# rgbMatrix.net
KiCad netlist of a schematic drawn in EAGLE
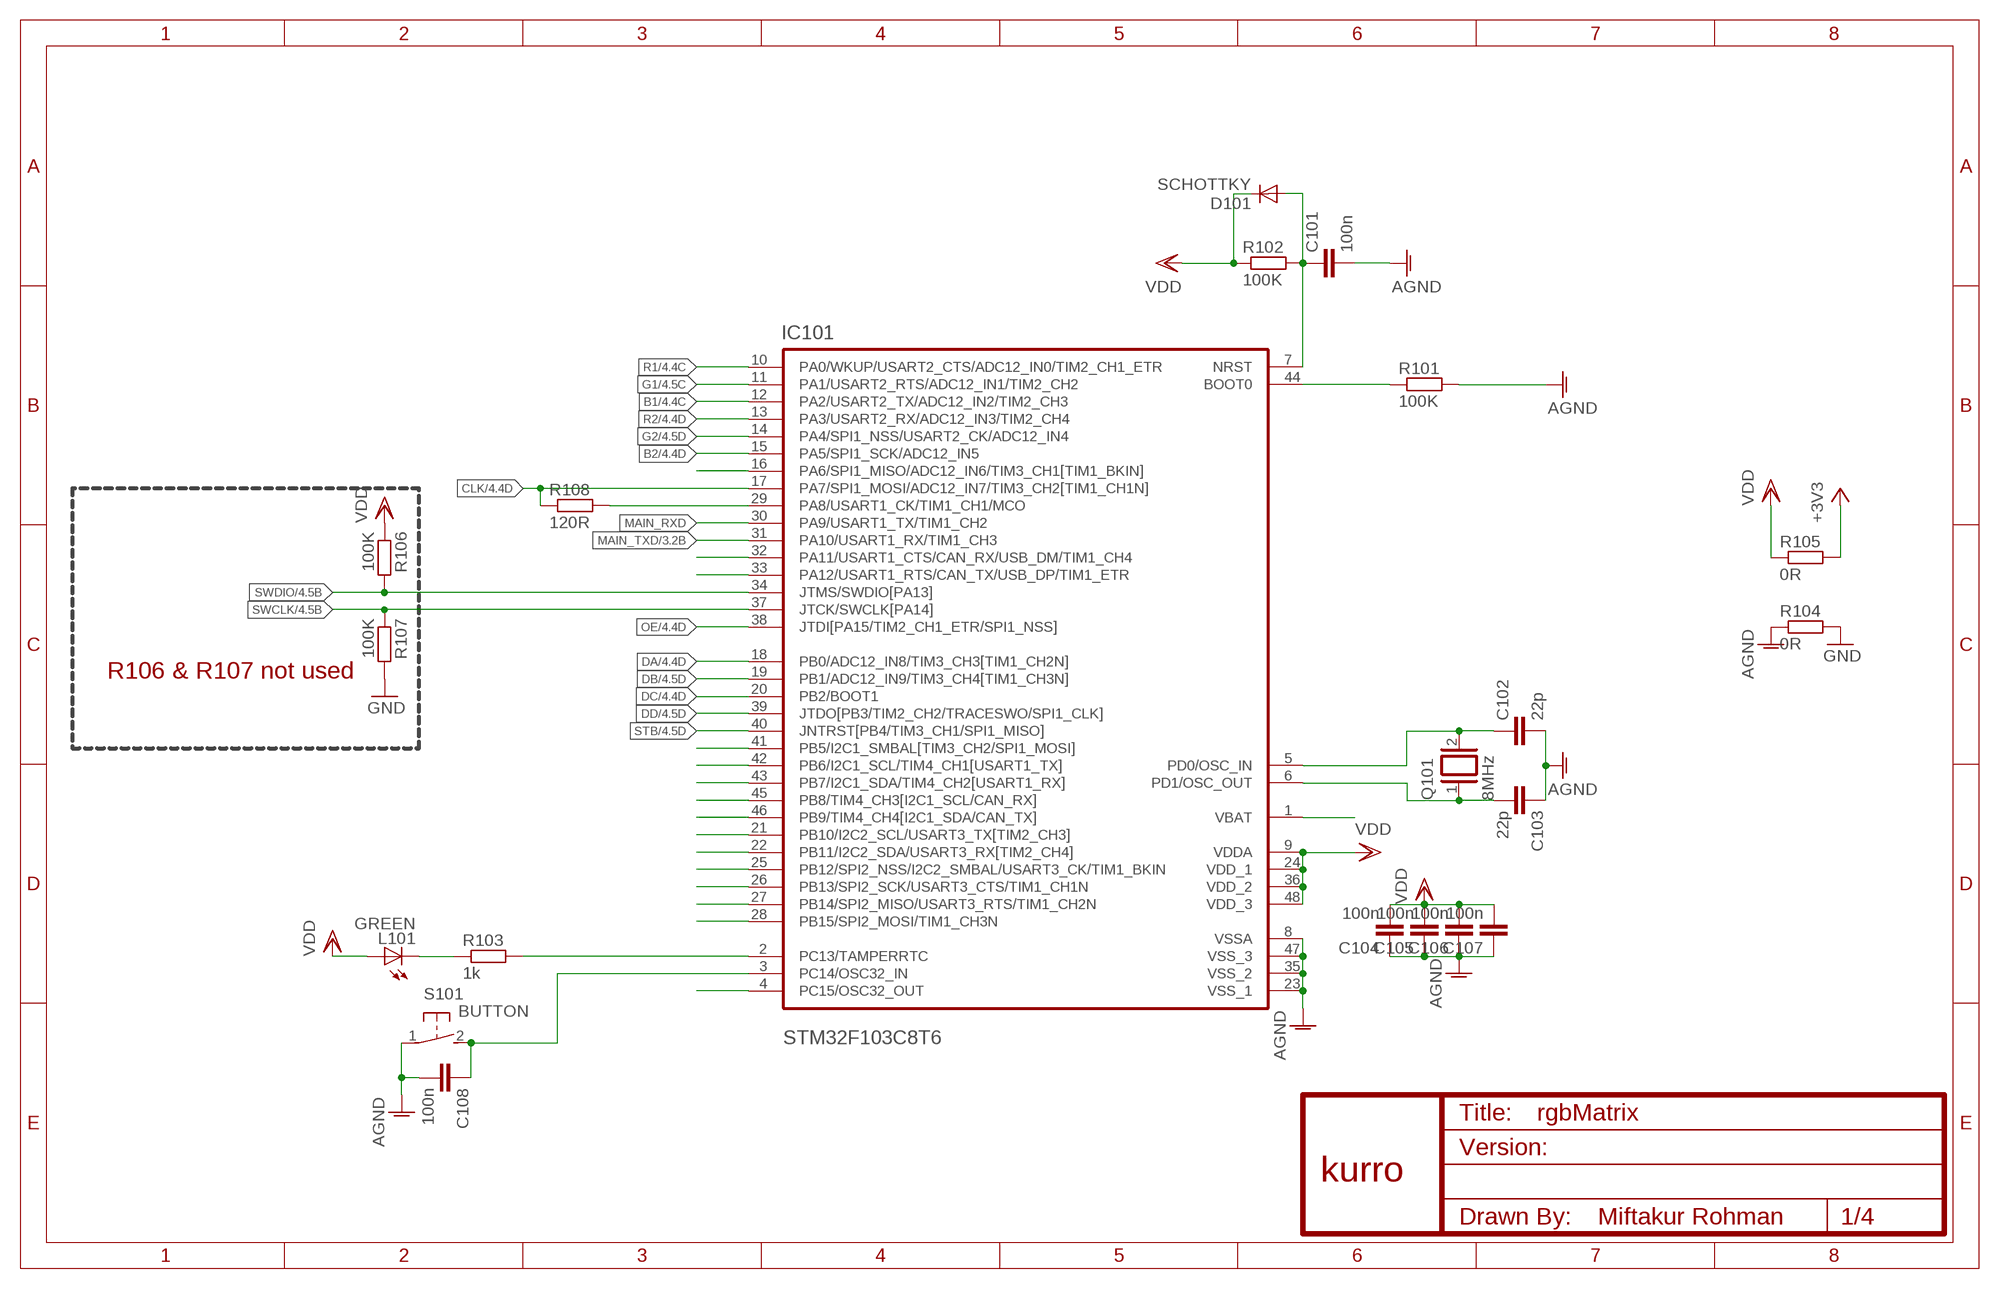
[diagram p0: schematic, sheet 1]
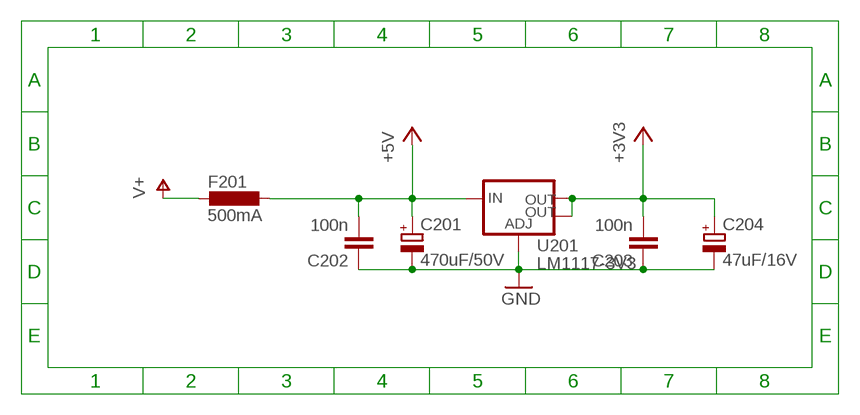
[diagram p1: schematic, sheet 2]
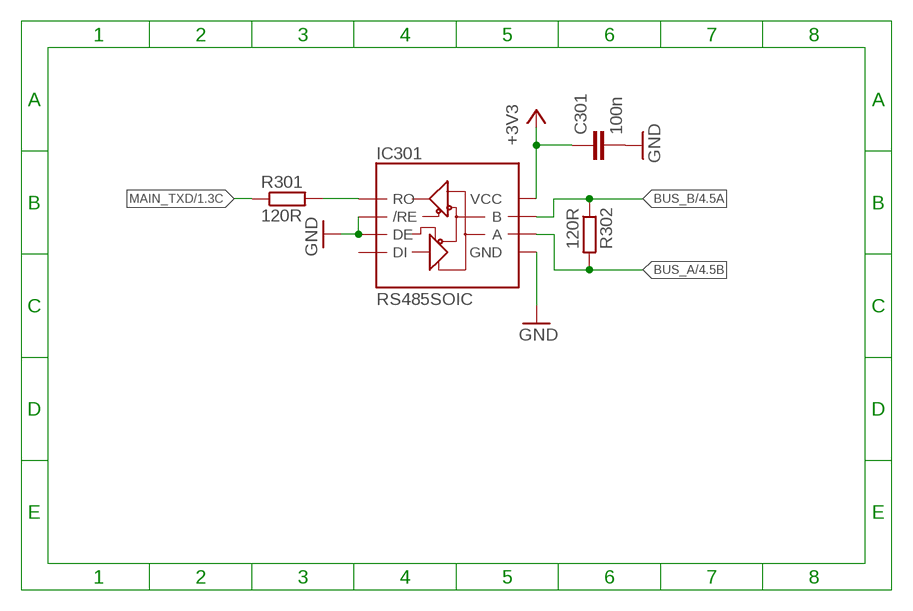
[diagram p2: schematic, sheet 3]
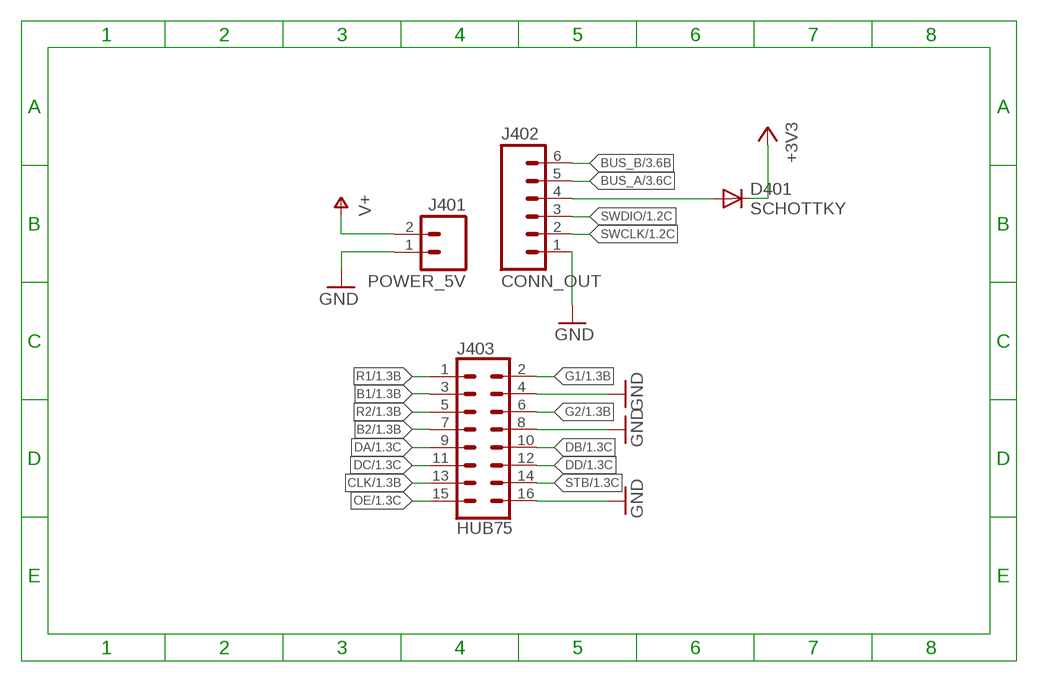
[diagram p3: schematic, sheet 4]

(export (version "E")
  (design (tool "Eeschema 10.0.6"))
  (components
    (comp (ref "C101")
      (value "100n")
      (footprint "eagle-import:C0603")
      (libsource (lib "eagle-import") (part "C-EUC0603"))
    )
    (comp (ref "C102")
      (value "22p")
      (footprint "eagle-import:C0603")
      (libsource (lib "eagle-import") (part "C-EUC0603"))
    )
    (comp (ref "C103")
      (value "22p")
      (footprint "eagle-import:C0603")
      (libsource (lib "eagle-import") (part "C-EUC0603"))
    )
    (comp (ref "C104")
      (value "100n")
      (footprint "eagle-import:C0603")
      (libsource (lib "eagle-import") (part "C-EUC0603"))
    )
    (comp (ref "C105")
      (value "100n")
      (footprint "eagle-import:C0603")
      (libsource (lib "eagle-import") (part "C-EUC0603"))
    )
    (comp (ref "C106")
      (value "100n")
      (footprint "eagle-import:C0603")
      (libsource (lib "eagle-import") (part "C-EUC0603"))
    )
    (comp (ref "C107")
      (value "100n")
      (footprint "eagle-import:C0603")
      (libsource (lib "eagle-import") (part "C-EUC0603"))
    )
    (comp (ref "C108")
      (value "100n")
      (footprint "eagle-import:C0603")
      (libsource (lib "eagle-import") (part "C-EUC0603"))
    )
    (comp (ref "D101")
      (value "SCHOTTKY")
      (footprint "eagle-import:MICROMELF-W")
      (libsource (lib "eagle-import") (part "DIODE-MICROMELF-W"))
    )
    (comp (ref "IC101")
      (value "STM32F103C8T6")
      (footprint "eagle-import:QFP50P900X900X160-48N")
      (fields (field (name "MPN") "STM32F103CBT6"))
      (libsource (lib "eagle-import") (part "STM32F103C8T6"))
    )
    (comp (ref "L101")
      (value "GREEN")
      (footprint "eagle-import:LED3MM")
      (libsource (lib "eagle-import") (part "LED3MM"))
    )
    (comp (ref "Q101")
      (value "8MHz")
      (footprint "eagle-import:QS")
      (libsource (lib "eagle-import") (part "XTAL/S"))
    )
    (comp (ref "R101")
      (value "100K")
      (footprint "eagle-import:R0603")
      (libsource (lib "eagle-import") (part "R-EU_R0603"))
    )
    (comp (ref "R102")
      (value "100K")
      (footprint "eagle-import:R0603")
      (libsource (lib "eagle-import") (part "R-EU_R0603"))
    )
    (comp (ref "R103")
      (value "1k")
      (footprint "eagle-import:R0603")
      (libsource (lib "eagle-import") (part "R-EU_R0603"))
    )
    (comp (ref "R104")
      (value "0R")
      (footprint "eagle-import:R0603")
      (libsource (lib "eagle-import") (part "R-EU_R0603"))
    )
    (comp (ref "R105")
      (value "0R")
      (footprint "eagle-import:R0603")
      (libsource (lib "eagle-import") (part "R-EU_R0603"))
    )
    (comp (ref "R106")
      (value "100K")
      (footprint "eagle-import:R0603")
      (libsource (lib "eagle-import") (part "R-EU_R0603"))
    )
    (comp (ref "R107")
      (value "100K")
      (footprint "eagle-import:R0603")
      (libsource (lib "eagle-import") (part "R-EU_R0603"))
    )
    (comp (ref "R108")
      (value "120R")
      (footprint "eagle-import:R0603")
      (libsource (lib "eagle-import") (part "R-EU_R0603"))
    )
    (comp (ref "S101")
      (value "BUTTON")
      (footprint "eagle-import:B3F-01XXX")
      (libsource (lib "eagle-import") (part "01-XX2"))
    )
    (comp (ref "U$1")
      (value "KURRO_FOOTPRINT")
      (footprint "eagle-import:KURRO-LOGO")
      (libsource (lib "eagle-import") (part "KURRO_FOOTPRINT"))
    )
    (comp (ref "C201")
      (value "470uF/50V")
      (footprint "eagle-import:E5-10,5")
      (libsource (lib "eagle-import") (part "CPOL-EUE5-10.5"))
    )
    (comp (ref "C202")
      (value "100n")
      (footprint "eagle-import:C0603")
      (libsource (lib "eagle-import") (part "C-EUC0603"))
    )
    (comp (ref "C203")
      (value "100n")
      (footprint "eagle-import:C0603")
      (libsource (lib "eagle-import") (part "C-EUC0603"))
    )
    (comp (ref "C204")
      (value "47uF/16V")
      (footprint "eagle-import:E2-5")
      (libsource (lib "eagle-import") (part "CPOL-EUE2-5"))
    )
    (comp (ref "F201")
      (value "500mA")
      (footprint "eagle-import:L1812")
      (libsource (lib "eagle-import") (part "L-EUL1812"))
    )
    (comp (ref "U201")
      (value "LM1117-3V3")
      (footprint "eagle-import:SOT223")
      (libsource (lib "eagle-import") (part "V_REG_LM1117SOT223"))
    )
    (comp (ref "C301")
      (value "100n")
      (footprint "eagle-import:C0603")
      (libsource (lib "eagle-import") (part "C-EUC0603"))
    )
    (comp (ref "IC301")
      (value "RS485SOIC")
      (footprint "eagle-import:SO08")
      (libsource (lib "eagle-import") (part "RS485SOIC"))
    )
    (comp (ref "R301")
      (value "120R")
      (footprint "eagle-import:R0603")
      (libsource (lib "eagle-import") (part "R-EU_R0603"))
    )
    (comp (ref "R302")
      (value "120R")
      (footprint "eagle-import:R0603")
      (libsource (lib "eagle-import") (part "R-EU_R0603"))
    )
    (comp (ref "D401")
      (value "SCHOTTKY")
      (footprint "eagle-import:MICROMELF-W")
      (libsource (lib "eagle-import") (part "DIODE-MICROMELF-W"))
    )
    (comp (ref "J401")
      (value "POWER_5V")
      (footprint "eagle-import:XH-2-RA")
      (libsource (lib "eagle-import") (part "M02-XH-RA"))
    )
    (comp (ref "J402")
      (value "CONN_OUT")
      (footprint "eagle-import:XH-6-RA")
      (libsource (lib "eagle-import") (part "M06-XH-RA"))
    )
    (comp (ref "J403")
      (value "HUB75")
      (footprint "eagle-import:2X08-LOCK")
      (libsource (lib "eagle-import") (part "PINHEAD-2X8"))
    )
  )
  (nets
    (net (code "1") (name "+3V3") (class "Default")
      (node (ref "C203") (pin "2") (pinfunction "2_2") (pintype "passive"))
      (node (ref "C204") (pin "+") (pinfunction "+_+") (pintype "passive"))
      (node (ref "C301") (pin "1") (pinfunction "1_1") (pintype "passive"))
      (node (ref "D401") (pin "C") (pinfunction "C_C") (pintype "passive"))
      (node (ref "IC301") (pin "8") (pinfunction "VCC_8") (pintype "bidirectional"))
      (node (ref "R105") (pin "2") (pinfunction "2_2") (pintype "passive"))
      (node (ref "U201") (pin "2") (pinfunction "OUT_2") (pintype "output"))
      (node (ref "U201") (pin "4") (pinfunction "OUT_4") (pintype "output"))
    )
    (net (code "2") (name "+5V") (class "Default")
      (node (ref "C201") (pin "+") (pinfunction "+_+") (pintype "passive"))
      (node (ref "C202") (pin "2") (pinfunction "2_2") (pintype "passive"))
      (node (ref "F201") (pin "1") (pinfunction "1_1") (pintype "passive"))
      (node (ref "U201") (pin "3") (pinfunction "IN_3") (pintype "input"))
    )
    (net (code "3") (name "AGND") (class "Default")
      (node (ref "C101") (pin "2") (pinfunction "2_2") (pintype "passive"))
      (node (ref "C102") (pin "2") (pinfunction "2_2") (pintype "passive"))
      (node (ref "C103") (pin "1") (pinfunction "1_1") (pintype "passive"))
      (node (ref "C104") (pin "1") (pinfunction "1_1") (pintype "passive"))
      (node (ref "C105") (pin "1") (pinfunction "1_1") (pintype "passive"))
      (node (ref "C106") (pin "1") (pinfunction "1_1") (pintype "passive"))
      (node (ref "C107") (pin "1") (pinfunction "1_1") (pintype "passive"))
      (node (ref "C108") (pin "2") (pinfunction "2_2") (pintype "passive"))
      (node (ref "IC101") (pin "23") (pinfunction "VSS_1_23") (pintype "bidirectional"))
      (node (ref "IC101") (pin "35") (pinfunction "VSS_2_35") (pintype "passive"))
      (node (ref "IC101") (pin "47") (pinfunction "VSS_3_47") (pintype "passive"))
      (node (ref "IC101") (pin "8") (pinfunction "VSSA_8") (pintype "passive"))
      (node (ref "R101") (pin "2") (pinfunction "2_2") (pintype "passive"))
      (node (ref "R104") (pin "1") (pinfunction "1_1") (pintype "passive"))
      (node (ref "S101") (pin "1") (pinfunction "P_1") (pintype "passive"))
    )
    (net (code "4") (name "B1") (class "Default")
      (node (ref "IC101") (pin "12") (pinfunction "PA2/USART2_TX/ADC12_IN2/TIM2_CH3_12") (pintype "bidirectional"))
      (node (ref "J403") (pin "3") (pinfunction "3_3") (pintype "passive"))
    )
    (net (code "5") (name "B2") (class "Default")
      (node (ref "IC101") (pin "15") (pinfunction "PA5/SPI1_SCK/ADC12_IN5_15") (pintype "bidirectional"))
      (node (ref "J403") (pin "7") (pinfunction "7_7") (pintype "passive"))
    )
    (net (code "6") (name "BUS_A") (class "Default")
      (node (ref "IC301") (pin "6") (pinfunction "A_6") (pintype "bidirectional"))
      (node (ref "J402") (pin "5") (pinfunction "5_5") (pintype "passive"))
      (node (ref "R302") (pin "2") (pinfunction "2_2") (pintype "passive"))
    )
    (net (code "7") (name "BUS_B") (class "Default")
      (node (ref "IC301") (pin "7") (pinfunction "B_7") (pintype "bidirectional"))
      (node (ref "J402") (pin "6") (pinfunction "6_6") (pintype "passive"))
      (node (ref "R302") (pin "1") (pinfunction "1_1") (pintype "passive"))
    )
    (net (code "8") (name "CLK") (class "Default")
      (node (ref "IC101") (pin "17") (pinfunction "PA7/SPI1_MOSI/ADC12_IN7/TIM3_CH2[TIM1_CH1N]_17") (pintype "bidirectional"))
      (node (ref "J403") (pin "13") (pinfunction "13_13") (pintype "passive"))
      (node (ref "R108") (pin "1") (pinfunction "1_1") (pintype "passive"))
    )
    (net (code "9") (name "DA") (class "Default")
      (node (ref "IC101") (pin "18") (pinfunction "PB0/ADC12_IN8/TIM3_CH3[TIM1_CH2N]_18") (pintype "bidirectional"))
      (node (ref "J403") (pin "9") (pinfunction "9_9") (pintype "passive"))
    )
    (net (code "10") (name "DB") (class "Default")
      (node (ref "IC101") (pin "19") (pinfunction "PB1/ADC12_IN9/TIM3_CH4[TIM1_CH3N]_19") (pintype "bidirectional"))
      (node (ref "J403") (pin "10") (pinfunction "10_10") (pintype "passive"))
    )
    (net (code "11") (name "DC") (class "Default")
      (node (ref "IC101") (pin "20") (pinfunction "PB2/BOOT1_20") (pintype "bidirectional"))
      (node (ref "J403") (pin "11") (pinfunction "11_11") (pintype "passive"))
    )
    (net (code "12") (name "DD") (class "Default")
      (node (ref "IC101") (pin "39") (pinfunction "JTDO[PB3/TIM2_CH2/TRACESWO/SPI1_CLK]_39") (pintype "bidirectional"))
      (node (ref "J403") (pin "12") (pinfunction "12_12") (pintype "passive"))
    )
    (net (code "13") (name "G1") (class "Default")
      (node (ref "IC101") (pin "11") (pinfunction "PA1/USART2_RTS/ADC12_IN1/TIM2_CH2_11") (pintype "bidirectional"))
      (node (ref "J403") (pin "2") (pinfunction "2_2") (pintype "passive"))
    )
    (net (code "14") (name "G2") (class "Default")
      (node (ref "IC101") (pin "14") (pinfunction "PA4/SPI1_NSS/USART2_CK/ADC12_IN4_14") (pintype "bidirectional"))
      (node (ref "J403") (pin "6") (pinfunction "6_6") (pintype "passive"))
    )
    (net (code "15") (name "GND") (class "Default")
      (node (ref "C201") (pin "-") (pinfunction "-_-") (pintype "passive"))
      (node (ref "C202") (pin "1") (pinfunction "1_1") (pintype "passive"))
      (node (ref "C203") (pin "1") (pinfunction "1_1") (pintype "passive"))
      (node (ref "C204") (pin "-") (pinfunction "-_-") (pintype "passive"))
      (node (ref "C301") (pin "2") (pinfunction "2_2") (pintype "passive"))
      (node (ref "IC301") (pin "2") (pinfunction "/RE_2") (pintype "bidirectional"))
      (node (ref "IC301") (pin "3") (pinfunction "DE_3") (pintype "bidirectional"))
      (node (ref "IC301") (pin "5") (pinfunction "GND_5") (pintype "bidirectional"))
      (node (ref "J401") (pin "1") (pinfunction "1_1") (pintype "passive"))
      (node (ref "J402") (pin "1") (pinfunction "1_1") (pintype "passive"))
      (node (ref "J403") (pin "16") (pinfunction "16_16") (pintype "passive"))
      (node (ref "J403") (pin "4") (pinfunction "4_4") (pintype "passive"))
      (node (ref "J403") (pin "8") (pinfunction "8_8") (pintype "passive"))
      (node (ref "R104") (pin "2") (pinfunction "2_2") (pintype "passive"))
      (node (ref "R107") (pin "2") (pinfunction "2_2") (pintype "passive"))
      (node (ref "U201") (pin "1") (pinfunction "ADJ_1") (pintype "input"))
    )
    (net (code "16") (name "MAIN_RXD") (class "Default")
      (node (ref "IC101") (pin "30") (pinfunction "PA9/USART1_TX/TIM1_CH2_30") (pintype "bidirectional"))
    )
    (net (code "17") (name "MAIN_TXD") (class "Default")
      (node (ref "IC101") (pin "31") (pinfunction "PA10/USART1_RX/TIM1_CH3_31") (pintype "bidirectional"))
      (node (ref "R301") (pin "1") (pinfunction "1_1") (pintype "passive"))
    )
    (net (code "18") (name "Net-(D401-PadA)") (class "Default")
      (node (ref "D401") (pin "A") (pinfunction "A_A") (pintype "passive"))
      (node (ref "J402") (pin "4") (pinfunction "4_4") (pintype "passive"))
    )
    (net (code "19") (name "Net-(IC101-BOOT0)") (class "Default")
      (node (ref "IC101") (pin "44") (pinfunction "BOOT0_44") (pintype "bidirectional"))
      (node (ref "R101") (pin "1") (pinfunction "1_1") (pintype "passive"))
    )
    (net (code "20") (name "Net-(IC101-NRST)") (class "Default")
      (node (ref "C101") (pin "1") (pinfunction "1_1") (pintype "passive"))
      (node (ref "D101") (pin "A") (pinfunction "A_A") (pintype "passive"))
      (node (ref "IC101") (pin "7") (pinfunction "NRST_7") (pintype "bidirectional"))
      (node (ref "R102") (pin "2") (pinfunction "2_2") (pintype "passive"))
    )
    (net (code "21") (name "Net-(IC101-PA8{slash}USART1_CK{slash}TIM1_CH1{slash}MCO)") (class "Default")
      (node (ref "IC101") (pin "29") (pinfunction "PA8/USART1_CK/TIM1_CH1/MCO_29") (pintype "bidirectional"))
      (node (ref "R108") (pin "2") (pinfunction "2_2") (pintype "passive"))
    )
    (net (code "22") (name "Net-(IC101-PC13{slash}TAMPERRTC)") (class "Default")
      (node (ref "IC101") (pin "2") (pinfunction "PC13/TAMPERRTC_2") (pintype "bidirectional"))
      (node (ref "R103") (pin "2") (pinfunction "2_2") (pintype "passive"))
    )
    (net (code "23") (name "Net-(IC101-PC14{slash}OSC32_IN)") (class "Default")
      (node (ref "C108") (pin "1") (pinfunction "1_1") (pintype "passive"))
      (node (ref "IC101") (pin "3") (pinfunction "PC14/OSC32_IN_3") (pintype "bidirectional"))
      (node (ref "S101") (pin "2") (pinfunction "S_2") (pintype "passive"))
    )
    (net (code "24") (name "Net-(IC101-PD0{slash}OSC_IN)") (class "Default")
      (node (ref "C102") (pin "1") (pinfunction "1_1") (pintype "passive"))
      (node (ref "IC101") (pin "5") (pinfunction "PD0/OSC_IN_5") (pintype "bidirectional"))
      (node (ref "Q101") (pin "2") (pinfunction "2_2") (pintype "passive"))
    )
    (net (code "25") (name "Net-(IC101-PD1{slash}OSC_OUT)") (class "Default")
      (node (ref "C103") (pin "2") (pinfunction "2_2") (pintype "passive"))
      (node (ref "IC101") (pin "6") (pinfunction "PD1/OSC_OUT_6") (pintype "bidirectional"))
      (node (ref "Q101") (pin "1") (pinfunction "1_1") (pintype "passive"))
    )
    (net (code "26") (name "Net-(IC301-RO)") (class "Default")
      (node (ref "IC301") (pin "1") (pinfunction "RO_1") (pintype "bidirectional"))
      (node (ref "R301") (pin "2") (pinfunction "2_2") (pintype "passive"))
    )
    (net (code "27") (name "Net-(L101-C)") (class "Default")
      (node (ref "L101") (pin "K") (pinfunction "C_K") (pintype "passive"))
      (node (ref "R103") (pin "1") (pinfunction "1_1") (pintype "passive"))
    )
    (net (code "28") (name "OE") (class "Default")
      (node (ref "IC101") (pin "38") (pinfunction "JTDI[PA15/TIM2_CH1_ETR/SPI1_NSS]_38") (pintype "bidirectional"))
      (node (ref "J403") (pin "15") (pinfunction "15_15") (pintype "passive"))
    )
    (net (code "29") (name "R1") (class "Default")
      (node (ref "IC101") (pin "10") (pinfunction "PA0/WKUP/USART2_CTS/ADC12_IN0/TIM2_CH1_ETR_10") (pintype "bidirectional"))
      (node (ref "J403") (pin "1") (pinfunction "1_1") (pintype "passive"))
    )
    (net (code "30") (name "R2") (class "Default")
      (node (ref "IC101") (pin "13") (pinfunction "PA3/USART2_RX/ADC12_IN3/TIM2_CH4_13") (pintype "bidirectional"))
      (node (ref "J403") (pin "5") (pinfunction "5_5") (pintype "passive"))
    )
    (net (code "31") (name "STB") (class "Default")
      (node (ref "IC101") (pin "40") (pinfunction "JNTRST[PB4/TIM3_CH1/SPI1_MISO]_40") (pintype "bidirectional"))
      (node (ref "J403") (pin "14") (pinfunction "14_14") (pintype "passive"))
    )
    (net (code "32") (name "SWCLK") (class "Default")
      (node (ref "IC101") (pin "37") (pinfunction "JTCK/SWCLK[PA14]_37") (pintype "bidirectional"))
      (node (ref "J402") (pin "2") (pinfunction "2_2") (pintype "passive"))
      (node (ref "R107") (pin "1") (pinfunction "1_1") (pintype "passive"))
    )
    (net (code "33") (name "SWDIO") (class "Default")
      (node (ref "IC101") (pin "34") (pinfunction "JTMS/SWDIO[PA13]_34") (pintype "bidirectional"))
      (node (ref "J402") (pin "3") (pinfunction "3_3") (pintype "passive"))
      (node (ref "R106") (pin "2") (pinfunction "2_2") (pintype "passive"))
    )
    (net (code "34") (name "V+") (class "Default")
      (node (ref "F201") (pin "2") (pinfunction "2_2") (pintype "passive"))
      (node (ref "J401") (pin "2") (pinfunction "2_2") (pintype "passive"))
    )
    (net (code "35") (name "VDD") (class "Default")
      (node (ref "C104") (pin "2") (pinfunction "2_2") (pintype "passive"))
      (node (ref "C105") (pin "2") (pinfunction "2_2") (pintype "passive"))
      (node (ref "C106") (pin "2") (pinfunction "2_2") (pintype "passive"))
      (node (ref "C107") (pin "2") (pinfunction "2_2") (pintype "passive"))
      (node (ref "D101") (pin "C") (pinfunction "C_C") (pintype "passive"))
      (node (ref "IC101") (pin "24") (pinfunction "VDD_1_24") (pintype "bidirectional"))
      (node (ref "IC101") (pin "36") (pinfunction "VDD_2_36") (pintype "power_in"))
      (node (ref "IC101") (pin "48") (pinfunction "VDD_3_48") (pintype "power_in"))
      (node (ref "IC101") (pin "9") (pinfunction "VDDA_9") (pintype "power_in"))
      (node (ref "L101") (pin "A") (pinfunction "A_A") (pintype "passive"))
      (node (ref "R102") (pin "1") (pinfunction "1_1") (pintype "passive"))
      (node (ref "R105") (pin "1") (pinfunction "1_1") (pintype "passive"))
      (node (ref "R106") (pin "1") (pinfunction "1_1") (pintype "passive"))
    )
    (net (code "36") (name "unconnected-(IC101-PA6{slash}SPI1_MISO{slash}ADC12_IN6{slash}TIM3_CH1[TIM1_BKIN]-Pad16)") (class "Default")
      (node (ref "IC101") (pin "16") (pinfunction "PA6/SPI1_MISO/ADC12_IN6/TIM3_CH1[TIM1_BKIN]_16") (pintype "bidirectional"))
    )
    (net (code "37") (name "unconnected-(IC101-PA11{slash}USART1_CTS{slash}CAN_RX{slash}USB_DM{slash}TIM1_CH4-Pad32)") (class "Default")
      (node (ref "IC101") (pin "32") (pinfunction "PA11/USART1_CTS/CAN_RX/USB_DM/TIM1_CH4_32") (pintype "power_in"))
    )
    (net (code "38") (name "unconnected-(IC101-PA12{slash}USART1_RTS{slash}CAN_TX{slash}USB_DP{slash}TIM1_ETR-Pad33)") (class "Default")
      (node (ref "IC101") (pin "33") (pinfunction "PA12/USART1_RTS/CAN_TX/USB_DP/TIM1_ETR_33") (pintype "bidirectional"))
    )
    (net (code "39") (name "unconnected-(IC101-PB5{slash}I2C1_SMBAL[TIM3_CH2{slash}SPI1_MOSI]-Pad41)") (class "Default")
      (node (ref "IC101") (pin "41") (pinfunction "PB5/I2C1_SMBAL[TIM3_CH2/SPI1_MOSI]_41") (pintype "bidirectional"))
    )
    (net (code "40") (name "unconnected-(IC101-PB6{slash}I2C1_SCL{slash}TIM4_CH1[USART1_TX]-Pad42)") (class "Default")
      (node (ref "IC101") (pin "42") (pinfunction "PB6/I2C1_SCL/TIM4_CH1[USART1_TX]_42") (pintype "bidirectional"))
    )
    (net (code "41") (name "unconnected-(IC101-PB7{slash}I2C1_SDA{slash}TIM4_CH2[USART1_RX]-Pad43)") (class "Default")
      (node (ref "IC101") (pin "43") (pinfunction "PB7/I2C1_SDA/TIM4_CH2[USART1_RX]_43") (pintype "bidirectional"))
    )
    (net (code "42") (name "unconnected-(IC101-PB8{slash}TIM4_CH3[I2C1_SCL{slash}CAN_RX]-Pad45)") (class "Default")
      (node (ref "IC101") (pin "45") (pinfunction "PB8/TIM4_CH3[I2C1_SCL/CAN_RX]_45") (pintype "bidirectional"))
    )
    (net (code "43") (name "unconnected-(IC101-PB9{slash}TIM4_CH4[I2C1_SDA{slash}CAN_TX]-Pad46)") (class "Default")
      (node (ref "IC101") (pin "46") (pinfunction "PB9/TIM4_CH4[I2C1_SDA/CAN_TX]_46") (pintype "bidirectional"))
    )
    (net (code "44") (name "unconnected-(IC101-PB10{slash}I2C2_SCL{slash}USART3_TX[TIM2_CH3]-Pad21)") (class "Default")
      (node (ref "IC101") (pin "21") (pinfunction "PB10/I2C2_SCL/USART3_TX[TIM2_CH3]_21") (pintype "bidirectional"))
    )
    (net (code "45") (name "unconnected-(IC101-PB11{slash}I2C2_SDA{slash}USART3_RX[TIM2_CH4]-Pad22)") (class "Default")
      (node (ref "IC101") (pin "22") (pinfunction "PB11/I2C2_SDA/USART3_RX[TIM2_CH4]_22") (pintype "bidirectional"))
    )
    (net (code "46") (name "unconnected-(IC101-PB12{slash}SPI2_NSS{slash}I2C2_SMBAL{slash}USART3_CK{slash}TIM1_BKIN-Pad25)") (class "Default")
      (node (ref "IC101") (pin "25") (pinfunction "PB12/SPI2_NSS/I2C2_SMBAL/USART3_CK/TIM1_BKIN_25") (pintype "bidirectional"))
    )
    (net (code "47") (name "unconnected-(IC101-PB13{slash}SPI2_SCK{slash}USART3_CTS{slash}TIM1_CH1N-Pad26)") (class "Default")
      (node (ref "IC101") (pin "26") (pinfunction "PB13/SPI2_SCK/USART3_CTS/TIM1_CH1N_26") (pintype "bidirectional"))
    )
    (net (code "48") (name "unconnected-(IC101-PB14{slash}SPI2_MISO{slash}USART3_RTS{slash}TIM1_CH2N-Pad27)") (class "Default")
      (node (ref "IC101") (pin "27") (pinfunction "PB14/SPI2_MISO/USART3_RTS/TIM1_CH2N_27") (pintype "bidirectional"))
    )
    (net (code "49") (name "unconnected-(IC101-PB15{slash}SPI2_MOSI{slash}TIM1_CH3N-Pad28)") (class "Default")
      (node (ref "IC101") (pin "28") (pinfunction "PB15/SPI2_MOSI/TIM1_CH3N_28") (pintype "bidirectional"))
    )
    (net (code "50") (name "unconnected-(IC101-PC15{slash}OSC32_OUT-Pad4)") (class "Default")
      (node (ref "IC101") (pin "4") (pinfunction "PC15/OSC32_OUT_4") (pintype "bidirectional"))
    )
    (net (code "51") (name "unconnected-(IC101-VBAT-Pad1)") (class "Default")
      (node (ref "IC101") (pin "1") (pinfunction "VBAT_1") (pintype "input"))
    )
    (net (code "52") (name "unconnected-(IC301-DI-Pad4)") (class "Default")
      (node (ref "IC301") (pin "4") (pinfunction "DI_4") (pintype "bidirectional"))
    )
  )
)
